# ISL6236A_DEMO.net
KiCad netlist of a schematic drawn in Altium Designer
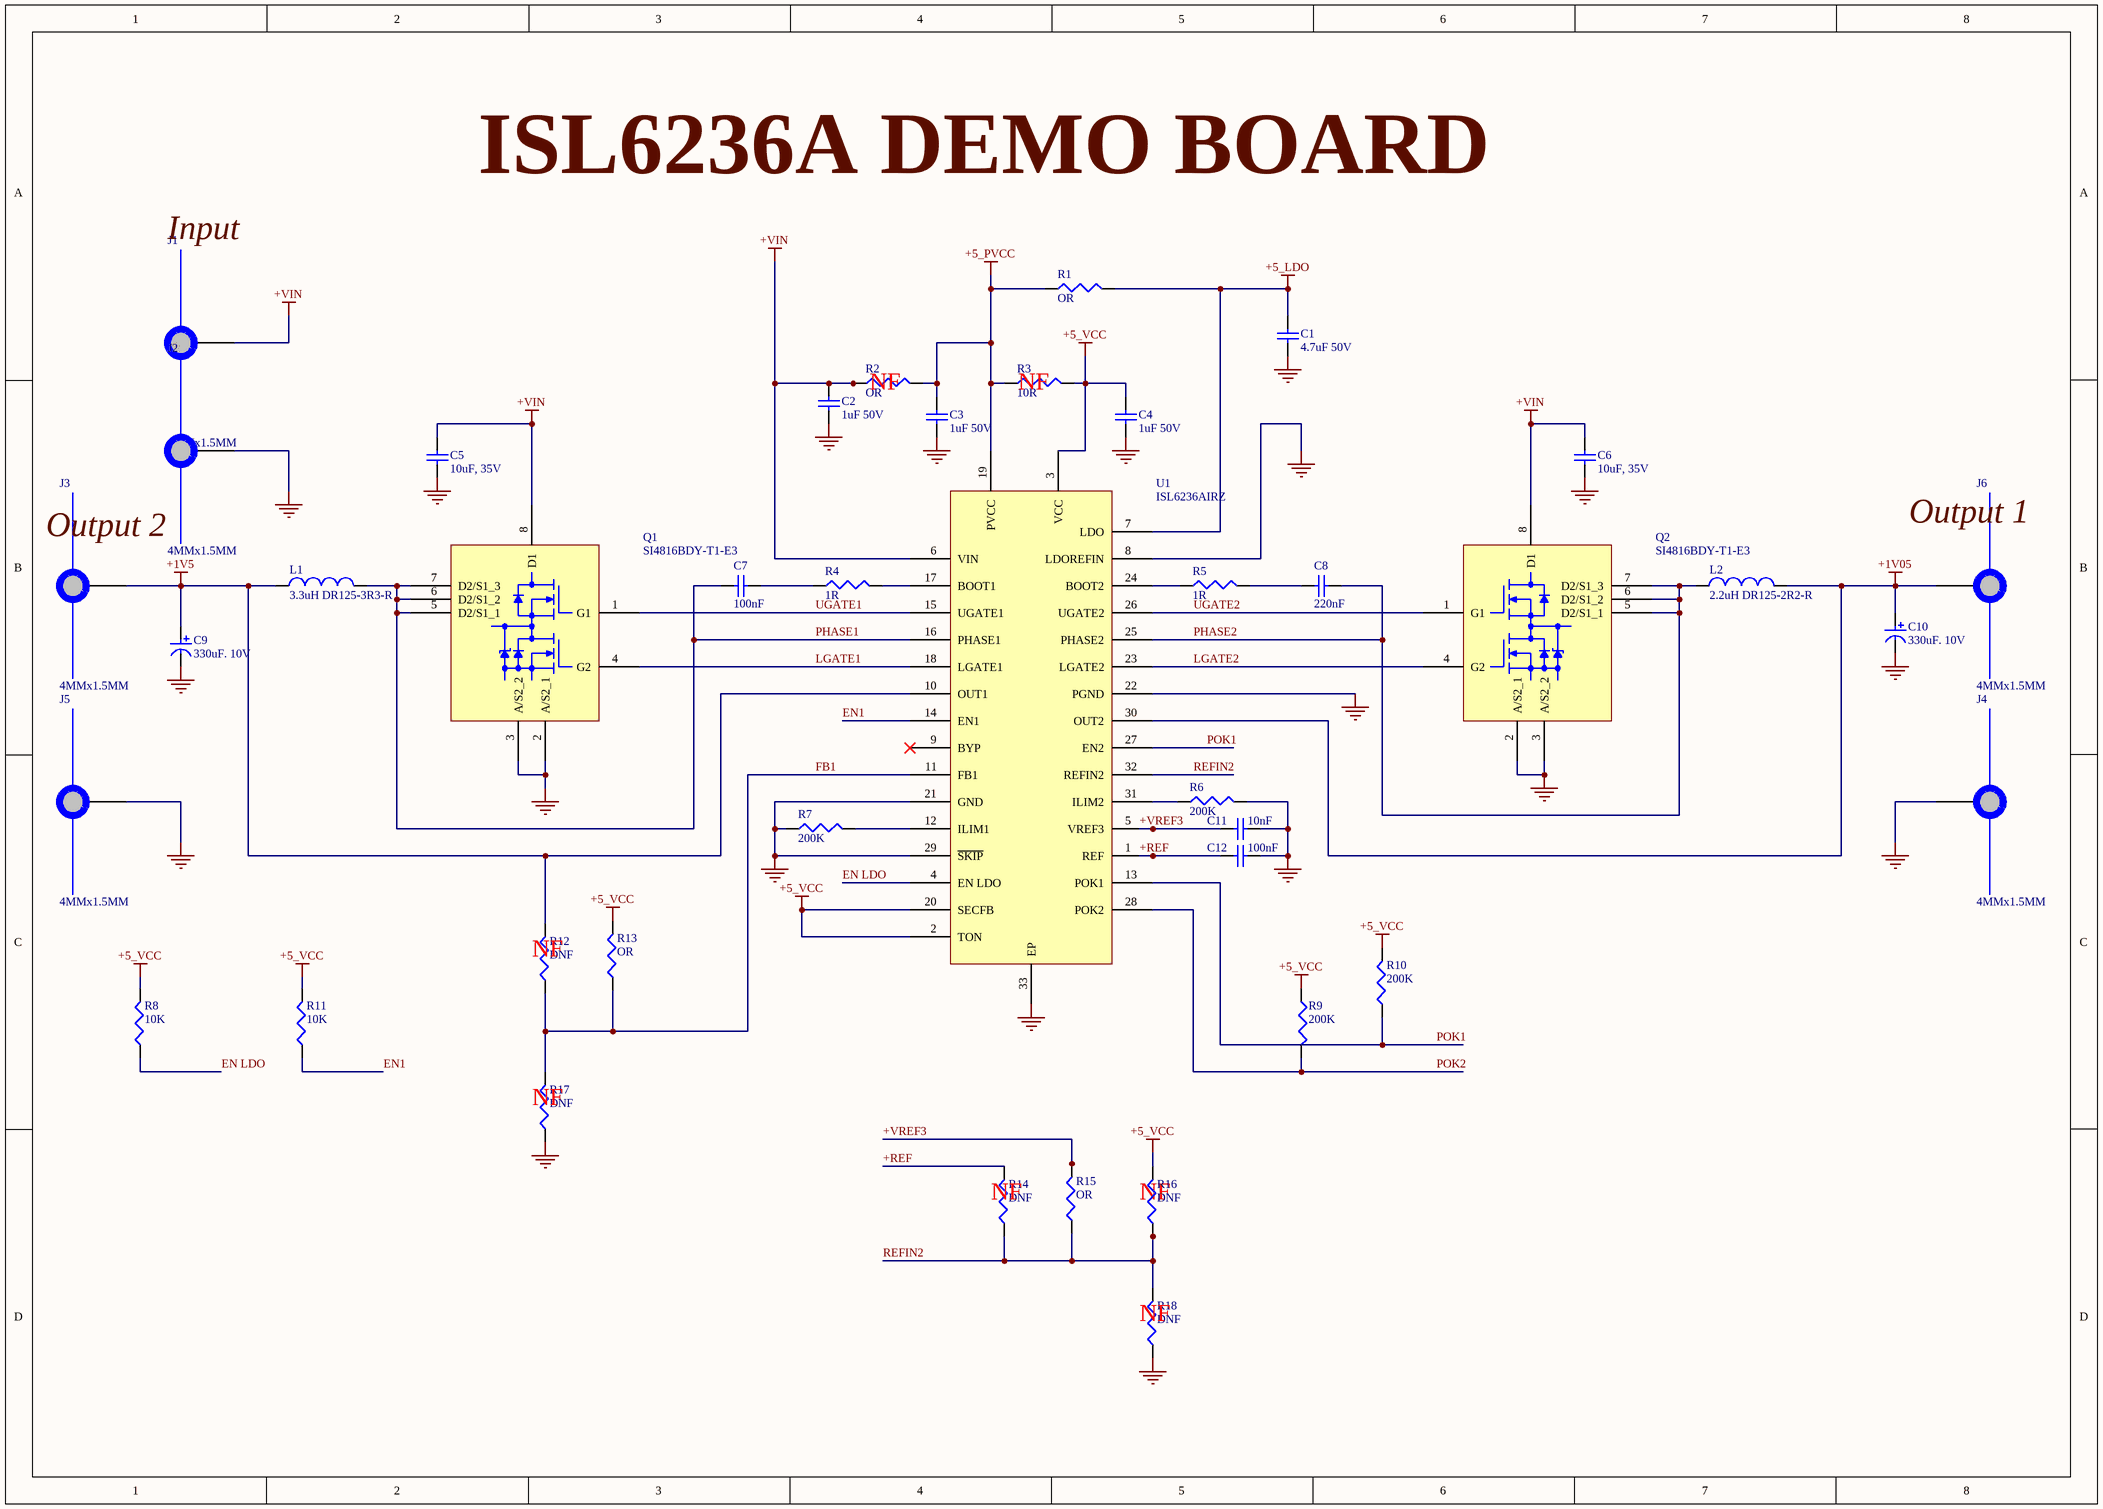
[diagram p0: ISL6236A_DEMO.SchDoc]

(export (version "E")
  (design (tool "Eeschema 10.0.6"))
  (components
    (comp (ref "C1")
      (value "4.7uF 50V")
      (footprint "C1206")
      (description "C Series 1206 4.7 uF 50 V ±10 % Tolerance X5R SMT Multilayer Ceramic Capacitor")
      (fields
        (field (name "MANUFACTURER") "TDK")
        (field (name "MANUFACTURER PART NUMBER") "C3216X5R1H475K160AB")
      )
      (libsource (lib "ISL6236A_DEMO") (part "C3216X5R1H475K160AB"))
    )
    (comp (ref "C2")
      (value "1uF 50V")
      (footprint "C0805")
      (description "Cap Ceramic 1uF 50V X7R 10% SMD 0805 125°C Embossed Plastic T/R")
      (fields
        (field (name "MANUFACTURER") "Samsung")
        (field (name "MANUFACTURER PART NUMBER") "CL21B105KBFNNNG")
      )
      (libsource (lib "ISL6236A_DEMO") (part "CL21B105KBFNNNG"))
    )
    (comp (ref "C3")
      (value "1uF 50V")
      (footprint "C0805")
      (description "Cap Ceramic 1uF 50V X7R 10% SMD 0805 125°C Embossed Plastic T/R")
      (fields
        (field (name "MANUFACTURER") "Samsung")
        (field (name "MANUFACTURER PART NUMBER") "CL21B105KBFNNNG")
      )
      (libsource (lib "ISL6236A_DEMO") (part "CL21B105KBFNNNG"))
    )
    (comp (ref "C4")
      (value "1uF 50V")
      (footprint "C0805")
      (description "Cap Ceramic 1uF 50V X7R 10% SMD 0805 125°C Embossed Plastic T/R")
      (fields
        (field (name "MANUFACTURER") "Samsung")
        (field (name "MANUFACTURER PART NUMBER") "CL21B105KBFNNNG")
      )
      (libsource (lib "ISL6236A_DEMO") (part "CL21B105KBFNNNG"))
    )
    (comp (ref "C5")
      (value "10uF, 35V")
      (footprint "C1210")
      (description "1210 C 10uF Ceramic Multilayer Capacitor; 35 VDC; +85degC; X5R Dielec; +/-10%")
      (fields
        (field (name "MANUFACTURER") "KEMET")
        (field (name "MANUFACTURER PART NUMBER") "C1210C106K6PACTU")
      )
      (libsource (lib "ISL6236A_DEMO") (part "C1210C106K6PACTU"))
    )
    (comp (ref "C6")
      (value "10uF, 35V")
      (footprint "C1210")
      (description "1210 C 10uF Ceramic Multilayer Capacitor; 35 VDC; +85degC; X5R Dielec; +/-10%")
      (fields
        (field (name "MANUFACTURER") "KEMET")
        (field (name "MANUFACTURER PART NUMBER") "C1210C106K6PACTU")
      )
      (libsource (lib "ISL6236A_DEMO") (part "C1210C106K6PACTU"))
    )
    (comp (ref "C7")
      (value "100nF")
      (footprint "C0805")
      (description "Cap Ceramic 0.1uF 50V X7R 10% SMD 2.0 x 1.2 mm 125 C Paper T/R")
      (fields
        (field (name "MANUFACTURER") "KEMET")
        (field (name "MANUFACTURER PART NUMBER") "C0805C104K5RACTU")
      )
      (libsource (lib "ISL6236A_DEMO") (part "C0805C104K5RACTU"))
    )
    (comp (ref "C8")
      (value "220nF")
      (footprint "C0805")
      (description "0805 C 220nF Ceramic Multilayer Capacitor; 50 VDC; +125degC; X7R Dielec; +/-10%")
      (fields
        (field (name "MANUFACTURER") "KEMET")
        (field (name "MANUFACTURER PART NUMBER") "C0805C224K5RACTU")
      )
      (libsource (lib "ISL6236A_DEMO") (part "C0805C224K5RACTU"))
    )
    (comp (ref "C9")
      (value "330uF. 10V")
      (footprint "7343-43")
      (description "Cap Tant Solid 330uF 10V X CASE 20% (7.3 X 4.3 X 4mm) SMD 7343-43 0.004 Ohm 125 C T/R")
      (fields
        (field (name "MANUFACTURER") "KEMET")
        (field (name "MANUFACTURER PART NUMBER") "T530X337M010AHE004")
      )
      (libsource (lib "ISL6236A_DEMO") (part "T530X337M010AHE004"))
    )
    (comp (ref "C10")
      (value "330uF. 10V")
      (footprint "7343-43")
      (description "Cap Tant Solid 330uF 10V X CASE 20% (7.3 X 4.3 X 4mm) SMD 7343-43 0.004 Ohm 125 C T/R")
      (fields
        (field (name "MANUFACTURER") "KEMET")
        (field (name "MANUFACTURER PART NUMBER") "T530X337M010AHE004")
      )
      (libsource (lib "ISL6236A_DEMO") (part "T530X337M010AHE004"))
    )
    (comp (ref "C11")
      (value "10nF")
      (footprint "C0805")
      (description "Cap Ceramic 0.01uF 50V X7R 10% SMD 0805 125C Plastic T/R")
      (fields
        (field (name "MANUFACTURER") "KEMET")
        (field (name "MANUFACTURER PART NUMBER") "C0805C103K5RACTU")
      )
      (libsource (lib "ISL6236A_DEMO") (part "C0805C103K5RACTU"))
    )
    (comp (ref "C12")
      (value "100nF")
      (footprint "C0805")
      (description "Cap Ceramic 0.1uF 50V X7R 10% SMD 2.0 x 1.2 mm 125 C Paper T/R")
      (fields
        (field (name "MANUFACTURER") "KEMET")
        (field (name "MANUFACTURER PART NUMBER") "C0805C104K5RACTU")
      )
      (libsource (lib "ISL6236A_DEMO") (part "C0805C104K5RACTU"))
    )
    (comp (ref "J1")
      (value "4MMx1.5MM")
      (footprint "PAD_WITH_HOLE_4MMx1MM5")
      (description "Pad with a hole 4mmx1.5mm")
      (libsource (lib "ISL6236A_DEMO") (part "PAD_WITH_HOLE_4MMx1MM5"))
    )
    (comp (ref "J2")
      (value "4MMx1.5MM")
      (footprint "PAD_WITH_HOLE_4MMx1MM5")
      (description "Pad with a hole 4mmx1.5mm")
      (libsource (lib "ISL6236A_DEMO") (part "PAD_WITH_HOLE_4MMx1MM5"))
    )
    (comp (ref "J3")
      (value "4MMx1.5MM")
      (footprint "PAD_WITH_HOLE_4MMx1MM5")
      (description "Pad with a hole 4mmx1.5mm")
      (libsource (lib "ISL6236A_DEMO") (part "PAD_WITH_HOLE_4MMx1MM5"))
    )
    (comp (ref "J4")
      (value "4MMx1.5MM")
      (footprint "PAD_WITH_HOLE_4MMx1MM5")
      (description "Pad with a hole 4mmx1.5mm")
      (libsource (lib "ISL6236A_DEMO") (part "PAD_WITH_HOLE_4MMx1MM5"))
    )
    (comp (ref "J5")
      (value "4MMx1.5MM")
      (footprint "PAD_WITH_HOLE_4MMx1MM5")
      (description "Pad with a hole 4mmx1.5mm")
      (libsource (lib "ISL6236A_DEMO") (part "PAD_WITH_HOLE_4MMx1MM5"))
    )
    (comp (ref "J6")
      (value "4MMx1.5MM")
      (footprint "PAD_WITH_HOLE_4MMx1MM5")
      (description "Pad with a hole 4mmx1.5mm")
      (libsource (lib "ISL6236A_DEMO") (part "PAD_WITH_HOLE_4MMx1MM5"))
    )
    (comp (ref "L1")
      (value "3.3uH DR125-3R3-R")
      (footprint "DR125")
      (description "Inductor Power Shielded Drum Core 3.3uH 20% 100KHz Ferrite 9.26A 6.3mOhm DCR T/R")
      (fields
        (field (name "MANUFACTURER") "Eaton Cooper")
        (field (name "MANUFACTURER PART NUMBER") "DR125-3R3-R")
      )
      (libsource (lib "ISL6236A_DEMO") (part "DR125-3R3-R"))
    )
    (comp (ref "L2")
      (value "2.2uH DR125-2R2-R")
      (footprint "DR125")
      (description "FIXED IND 2.2UH 10.9A 4.5 MOHM")
      (fields
        (field (name "MANUFACTURER") "Eaton Cooper")
        (field (name "MANUFACTURER PART NUMBER") "DR125-2R2-R")
      )
      (libsource (lib "ISL6236A_DEMO") (part "DR125-2R2-R"))
    )
    (comp (ref "Q1")
      (value "SI4816BDY-T1-E3")
      (footprint "SO-8")
      (description "Trans Mosfet N-ch 30V 5.8A/8.2A 8-PIN SOIC N T/r")
      (fields (field (name "MANUFACTURER") "Vishay Siliconix"))
      (libsource (lib "ISL6236A_DEMO") (part "SI4816BDY-T1-E3"))
    )
    (comp (ref "Q2")
      (value "SI4816BDY-T1-E3")
      (footprint "SO-8")
      (description "Trans Mosfet N-ch 30V 5.8A/8.2A 8-PIN SOIC N T/r")
      (fields (field (name "MANUFACTURER") "Vishay Siliconix"))
      (libsource (lib "") (part "SI4816BDY-T1-E3_1"))
    )
    (comp (ref "R1")
      (value "OR")
      (footprint "R0805")
      (description "Fixed Resistor, Metal Glaze/thick Film, 0.125W, 0ohm, Surface Mount, 0805")
      (fields
        (field (name "MANUFACTURER") "Yageo")
        (field (name "MANUFACTURER PART NUMBER") "AC0805JR-070RL")
      )
      (libsource (lib "ISL6236A_DEMO") (part "AC0805JR-070RL"))
    )
    (comp (ref "R2")
      (value "OR")
      (footprint "R0805")
      (description "Fixed Resistor, Metal Glaze/thick Film, 0.125W, 0ohm, Surface Mount, 0805")
      (fields
        (field (name "MANUFACTURER") "Yageo")
        (field (name "MANUFACTURER PART NUMBER") "AC0805JR-070RL")
      )
      (libsource (lib "ISL6236A_DEMO") (part "AC0805JR-070RL"))
    )
    (comp (ref "R3")
      (value "10R")
      (footprint "R0805")
      (description "Res Thick Film 0805 10 Ohm 1% 0.125W(1/8W) ±200ppm/C Pad SMD Automotive T/R")
      (fields
        (field (name "MANUFACTURER") "Yageo")
        (field (name "MANUFACTURER PART NUMBER") "AC0805FR-0710RL")
      )
      (libsource (lib "ISL6236A_DEMO") (part "AC0805FR-0710RL"))
    )
    (comp (ref "R4")
      (value "1R")
      (footprint "R0805")
      (description "Res Thick Film 0805 1 Ohm 1% 0.125W(1/8W) ±200ppm/C Pad SMD Automotive T/R")
      (fields
        (field (name "MANUFACTURER") "Yageo")
        (field (name "MANUFACTURER PART NUMBER") "AC0805FR-071RL")
      )
      (libsource (lib "ISL6236A_DEMO") (part "AC0805FR-071RL"))
    )
    (comp (ref "R5")
      (value "1R")
      (footprint "R0805")
      (description "Res Thick Film 0805 1 Ohm 1% 0.125W(1/8W) ±200ppm/C Pad SMD Automotive T/R")
      (fields
        (field (name "MANUFACTURER") "Yageo")
        (field (name "MANUFACTURER PART NUMBER") "AC0805FR-071RL")
      )
      (libsource (lib "ISL6236A_DEMO") (part "AC0805FR-071RL"))
    )
    (comp (ref "R6")
      (value "200K")
      (footprint "R0805")
      (description "Res Thick Film 0805 200K Ohm 1% 0.125W(1/8W) ±100ppm/C Pad SMD Automotive T/R")
      (fields
        (field (name "MANUFACTURER") "Yageo")
        (field (name "MANUFACTURER PART NUMBER") "AC0805FR-07200KL")
      )
      (libsource (lib "ISL6236A_DEMO") (part "AC0805FR-07200KL"))
    )
    (comp (ref "R7")
      (value "200K")
      (footprint "R0805")
      (description "Res Thick Film 0805 200K Ohm 1% 0.125W(1/8W) ±100ppm/C Pad SMD Automotive T/R")
      (fields
        (field (name "MANUFACTURER") "Yageo")
        (field (name "MANUFACTURER PART NUMBER") "AC0805FR-07200KL")
      )
      (libsource (lib "ISL6236A_DEMO") (part "AC0805FR-07200KL"))
    )
    (comp (ref "R8")
      (value "10K")
      (footprint "R0805")
      (description "Res Thick Film 0805 10K Ohm 1% 0.125W(1/8W) ±100ppm/C Pad SMD Automotive T/R")
      (fields
        (field (name "MANUFACTURER") "Yageo")
        (field (name "MANUFACTURER PART NUMBER") "AC0805FR-0710KL")
      )
      (libsource (lib "ISL6236A_DEMO") (part "AC0805FR-0710KL"))
    )
    (comp (ref "R9")
      (value "200K")
      (footprint "R0805")
      (description "Res Thick Film 0805 200K Ohm 1% 0.125W(1/8W) ±100ppm/C Pad SMD Automotive T/R")
      (fields
        (field (name "MANUFACTURER") "Yageo")
        (field (name "MANUFACTURER PART NUMBER") "AC0805FR-07200KL")
      )
      (libsource (lib "ISL6236A_DEMO") (part "AC0805FR-07200KL"))
    )
    (comp (ref "R10")
      (value "200K")
      (footprint "R0805")
      (description "Res Thick Film 0805 200K Ohm 1% 0.125W(1/8W) ±100ppm/C Pad SMD Automotive T/R")
      (fields
        (field (name "MANUFACTURER") "Yageo")
        (field (name "MANUFACTURER PART NUMBER") "AC0805FR-07200KL")
      )
      (libsource (lib "ISL6236A_DEMO") (part "AC0805FR-07200KL"))
    )
    (comp (ref "R11")
      (value "10K")
      (footprint "R0805")
      (description "Res Thick Film 0805 10K Ohm 1% 0.125W(1/8W) ±100ppm/C Pad SMD Automotive T/R")
      (fields
        (field (name "MANUFACTURER") "Yageo")
        (field (name "MANUFACTURER PART NUMBER") "AC0805FR-0710KL")
      )
      (libsource (lib "ISL6236A_DEMO") (part "AC0805FR-0710KL"))
    )
    (comp (ref "R12") (value "DNF") (footprint "R0805") (libsource (lib "ISL6236A_DEMO") (part "RES")))
    (comp (ref "R13")
      (value "OR")
      (footprint "R0805")
      (description "Fixed Resistor, Metal Glaze/thick Film, 0.125W, 0ohm, Surface Mount, 0805")
      (fields
        (field (name "MANUFACTURER") "Yageo")
        (field (name "MANUFACTURER PART NUMBER") "AC0805JR-070RL")
      )
      (libsource (lib "ISL6236A_DEMO") (part "AC0805JR-070RL"))
    )
    (comp (ref "R14") (value "DNF") (footprint "R0805") (libsource (lib "ISL6236A_DEMO") (part "RES")))
    (comp (ref "R15")
      (value "OR")
      (footprint "R0805")
      (description "Fixed Resistor, Metal Glaze/thick Film, 0.125W, 0ohm, Surface Mount, 0805")
      (fields
        (field (name "MANUFACTURER") "Yageo")
        (field (name "MANUFACTURER PART NUMBER") "AC0805JR-070RL")
      )
      (libsource (lib "ISL6236A_DEMO") (part "AC0805JR-070RL"))
    )
    (comp (ref "R16") (value "DNF") (footprint "R0805") (libsource (lib "ISL6236A_DEMO") (part "RES")))
    (comp (ref "R17") (value "DNF") (footprint "R0805") (libsource (lib "ISL6236A_DEMO") (part "RES")))
    (comp (ref "R18") (value "DNF") (footprint "R0805") (libsource (lib "ISL6236A_DEMO") (part "RES")))
    (comp (ref "U1")
      (value "ISL6236AIRZ")
      (footprint "L32.5x5B")
      (description "Soft Sw PWM Cntrlr 2-OUT Power Supply Controller 200KHz/300KHz/400KHz/500KHz 32-Pin QFN EP")
      (fields (field (name "MANUFACTURER") "Renesas"))
      (libsource (lib "ISL6236A_DEMO") (part "ISL6236AIRZ"))
    )
  )
  (nets
    (net (code "1") (name "+1V05") (class "Default")
      (node (ref "C10") (pin "1") (pinfunction "1_1") (pintype "passive"))
      (node (ref "J6") (pin "1") (pinfunction "1_1") (pintype "passive"))
      (node (ref "L2") (pin "2") (pinfunction "2_2") (pintype "passive"))
      (node (ref "U1") (pin "30") (pinfunction "OUT2_30") (pintype "passive"))
    )
    (net (code "2") (name "+1V5") (class "Default")
      (node (ref "C9") (pin "1") (pinfunction "1_1") (pintype "passive"))
      (node (ref "J3") (pin "1") (pinfunction "1_1") (pintype "passive"))
      (node (ref "L1") (pin "1") (pinfunction "1_1") (pintype "passive"))
      (node (ref "R12") (pin "2") (pinfunction "2_2") (pintype "passive"))
      (node (ref "U1") (pin "10") (pinfunction "OUT1_10") (pintype "passive"))
    )
    (net (code "3") (name "+5_LDO") (class "Default")
      (node (ref "C1") (pin "2") (pinfunction "2_2") (pintype "passive"))
      (node (ref "R1") (pin "2") (pinfunction "2_2") (pintype "passive"))
      (node (ref "U1") (pin "7") (pinfunction "LDO_7") (pintype "passive"))
    )
    (net (code "4") (name "+5_PVCC") (class "Default")
      (node (ref "C3") (pin "2") (pinfunction "2_2") (pintype "passive"))
      (node (ref "R1") (pin "1") (pinfunction "1_1") (pintype "passive"))
      (node (ref "R2") (pin "2") (pinfunction "2_2") (pintype "passive"))
      (node (ref "R3") (pin "1") (pinfunction "1_1") (pintype "passive"))
      (node (ref "U1") (pin "19") (pinfunction "PVCC_19") (pintype "passive"))
    )
    (net (code "5") (name "+5_VCC") (class "Default")
      (node (ref "C4") (pin "2") (pinfunction "2_2") (pintype "passive"))
      (node (ref "R10") (pin "2") (pinfunction "2_2") (pintype "passive"))
      (node (ref "R11") (pin "2") (pinfunction "2_2") (pintype "passive"))
      (node (ref "R13") (pin "2") (pinfunction "2_2") (pintype "passive"))
      (node (ref "R16") (pin "2") (pinfunction "2_2") (pintype "passive"))
      (node (ref "R3") (pin "2") (pinfunction "2_2") (pintype "passive"))
      (node (ref "R8") (pin "2") (pinfunction "2_2") (pintype "passive"))
      (node (ref "R9") (pin "1") (pinfunction "1_1") (pintype "passive"))
      (node (ref "U1") (pin "2") (pinfunction "TON_2") (pintype "passive"))
      (node (ref "U1") (pin "20") (pinfunction "SECFB_20") (pintype "passive"))
      (node (ref "U1") (pin "3") (pinfunction "VCC_3") (pintype "passive"))
    )
    (net (code "6") (name "+VIN") (class "Default")
      (node (ref "C2") (pin "2") (pinfunction "2_2") (pintype "passive"))
      (node (ref "C5") (pin "2") (pinfunction "2_2") (pintype "passive"))
      (node (ref "C6") (pin "2") (pinfunction "2_2") (pintype "passive"))
      (node (ref "J1") (pin "1") (pinfunction "1_1") (pintype "passive"))
      (node (ref "Q1") (pin "8") (pinfunction "D1_8") (pintype "passive"))
      (node (ref "Q2") (pin "8") (pinfunction "D1_8") (pintype "passive"))
      (node (ref "R2") (pin "1") (pinfunction "1_1") (pintype "passive"))
      (node (ref "U1") (pin "6") (pinfunction "VIN_6") (pintype "passive"))
    )
    (net (code "7") (name "/+REF") (class "Default")
      (node (ref "C12") (pin "1") (pinfunction "1_1") (pintype "passive"))
      (node (ref "R14") (pin "2") (pinfunction "2_2") (pintype "passive"))
      (node (ref "U1") (pin "1") (pinfunction "REF_1") (pintype "passive"))
    )
    (net (code "8") (name "/+VREF3") (class "Default")
      (node (ref "C11") (pin "1") (pinfunction "1_1") (pintype "passive"))
      (node (ref "R15") (pin "2") (pinfunction "2_2") (pintype "passive"))
      (node (ref "U1") (pin "5") (pinfunction "VREF3_5") (pintype "passive"))
    )
    (net (code "9") (name "/EN LDO") (class "Default")
      (node (ref "R8") (pin "1") (pinfunction "1_1") (pintype "passive"))
      (node (ref "U1") (pin "4") (pinfunction "EN_LDO_4") (pintype "passive"))
    )
    (net (code "10") (name "/EN1") (class "Default")
      (node (ref "R11") (pin "1") (pinfunction "1_1") (pintype "passive"))
      (node (ref "U1") (pin "14") (pinfunction "EN1_14") (pintype "passive"))
    )
    (net (code "11") (name "/FB1") (class "Default")
      (node (ref "R12") (pin "1") (pinfunction "1_1") (pintype "passive"))
      (node (ref "R13") (pin "1") (pinfunction "1_1") (pintype "passive"))
      (node (ref "R17") (pin "2") (pinfunction "2_2") (pintype "passive"))
      (node (ref "U1") (pin "11") (pinfunction "FB1_11") (pintype "passive"))
    )
    (net (code "12") (name "/LGATE1") (class "Default")
      (node (ref "Q1") (pin "4") (pinfunction "G2_4") (pintype "passive"))
      (node (ref "U1") (pin "18") (pinfunction "LGATE1_18") (pintype "passive"))
    )
    (net (code "13") (name "/LGATE2") (class "Default")
      (node (ref "Q2") (pin "4") (pinfunction "G2_4") (pintype "passive"))
      (node (ref "U1") (pin "23") (pinfunction "LGATE2_23") (pintype "passive"))
    )
    (net (code "14") (name "/PHASE1") (class "Default")
      (node (ref "C7") (pin "1") (pinfunction "1_1") (pintype "passive"))
      (node (ref "L1") (pin "2") (pinfunction "2_2") (pintype "passive"))
      (node (ref "Q1") (pin "5") (pinfunction "D2/S1_1_5") (pintype "passive"))
      (node (ref "Q1") (pin "6") (pinfunction "D2/S1_2_6") (pintype "passive"))
      (node (ref "Q1") (pin "7") (pinfunction "D2/S1_3_7") (pintype "passive"))
      (node (ref "U1") (pin "16") (pinfunction "PHASE1_16") (pintype "passive"))
    )
    (net (code "15") (name "/PHASE2") (class "Default")
      (node (ref "C8") (pin "2") (pinfunction "2_2") (pintype "passive"))
      (node (ref "L2") (pin "1") (pinfunction "1_1") (pintype "passive"))
      (node (ref "Q2") (pin "5") (pinfunction "D2/S1_1_5") (pintype "passive"))
      (node (ref "Q2") (pin "6") (pinfunction "D2/S1_2_6") (pintype "passive"))
      (node (ref "Q2") (pin "7") (pinfunction "D2/S1_3_7") (pintype "passive"))
      (node (ref "U1") (pin "25") (pinfunction "PHASE2_25") (pintype "passive"))
    )
    (net (code "16") (name "/POK1") (class "Default")
      (node (ref "R10") (pin "1") (pinfunction "1_1") (pintype "passive"))
      (node (ref "U1") (pin "13") (pinfunction "POK1_13") (pintype "passive"))
      (node (ref "U1") (pin "27") (pinfunction "EN2_27") (pintype "passive"))
    )
    (net (code "17") (name "/POK2") (class "Default")
      (node (ref "R9") (pin "2") (pinfunction "2_2") (pintype "passive"))
      (node (ref "U1") (pin "28") (pinfunction "POK2_28") (pintype "passive"))
    )
    (net (code "18") (name "/REFIN2") (class "Default")
      (node (ref "R14") (pin "1") (pinfunction "1_1") (pintype "passive"))
      (node (ref "R15") (pin "1") (pinfunction "1_1") (pintype "passive"))
      (node (ref "R16") (pin "1") (pinfunction "1_1") (pintype "passive"))
      (node (ref "R18") (pin "2") (pinfunction "2_2") (pintype "passive"))
      (node (ref "U1") (pin "32") (pinfunction "REFIN2_32") (pintype "passive"))
    )
    (net (code "19") (name "/UGATE1") (class "Default")
      (node (ref "Q1") (pin "1") (pinfunction "G1_1") (pintype "passive"))
      (node (ref "U1") (pin "15") (pinfunction "UGATE1_15") (pintype "passive"))
    )
    (net (code "20") (name "/UGATE2") (class "Default")
      (node (ref "Q2") (pin "1") (pinfunction "G1_1") (pintype "passive"))
      (node (ref "U1") (pin "26") (pinfunction "UGATE2_26") (pintype "passive"))
    )
    (net (code "21") (name "GND") (class "Default")
      (node (ref "C1") (pin "1") (pinfunction "1_1") (pintype "passive"))
      (node (ref "C10") (pin "2") (pinfunction "2_2") (pintype "passive"))
      (node (ref "C11") (pin "2") (pinfunction "2_2") (pintype "passive"))
      (node (ref "C12") (pin "2") (pinfunction "2_2") (pintype "passive"))
      (node (ref "C2") (pin "1") (pinfunction "1_1") (pintype "passive"))
      (node (ref "C3") (pin "1") (pinfunction "1_1") (pintype "passive"))
      (node (ref "C4") (pin "1") (pinfunction "1_1") (pintype "passive"))
      (node (ref "C5") (pin "1") (pinfunction "1_1") (pintype "passive"))
      (node (ref "C6") (pin "1") (pinfunction "1_1") (pintype "passive"))
      (node (ref "C9") (pin "2") (pinfunction "2_2") (pintype "passive"))
      (node (ref "J2") (pin "1") (pinfunction "1_1") (pintype "passive"))
      (node (ref "J4") (pin "1") (pinfunction "1_1") (pintype "passive"))
      (node (ref "J5") (pin "1") (pinfunction "1_1") (pintype "passive"))
      (node (ref "Q1") (pin "2") (pinfunction "A/S2_1_2") (pintype "passive"))
      (node (ref "Q1") (pin "3") (pinfunction "A/S2_2_3") (pintype "passive"))
      (node (ref "Q2") (pin "2") (pinfunction "A/S2_1_2") (pintype "passive"))
      (node (ref "Q2") (pin "3") (pinfunction "A/S2_2_3") (pintype "passive"))
      (node (ref "R17") (pin "1") (pinfunction "1_1") (pintype "passive"))
      (node (ref "R18") (pin "1") (pinfunction "1_1") (pintype "passive"))
      (node (ref "R6") (pin "2") (pinfunction "2_2") (pintype "passive"))
      (node (ref "R7") (pin "1") (pinfunction "1_1") (pintype "passive"))
      (node (ref "U1") (pin "21") (pinfunction "GND_21") (pintype "passive"))
      (node (ref "U1") (pin "22") (pinfunction "PGND_22") (pintype "passive"))
      (node (ref "U1") (pin "29") (pinfunction "~{SKIP}_29") (pintype "passive"))
      (node (ref "U1") (pin "33") (pinfunction "EP_33") (pintype "passive"))
      (node (ref "U1") (pin "8") (pinfunction "LDOREFIN_8") (pintype "passive"))
    )
    (net (code "22") (name "Net-(C7-Pad2)") (class "Default")
      (node (ref "C7") (pin "2") (pinfunction "2_2") (pintype "passive"))
      (node (ref "R4") (pin "1") (pinfunction "1_1") (pintype "passive"))
    )
    (net (code "23") (name "Net-(C8-Pad1)") (class "Default")
      (node (ref "C8") (pin "1") (pinfunction "1_1") (pintype "passive"))
      (node (ref "R5") (pin "2") (pinfunction "2_2") (pintype "passive"))
    )
    (net (code "24") (name "Net-(U1-BOOT1)") (class "Default")
      (node (ref "R4") (pin "2") (pinfunction "2_2") (pintype "passive"))
      (node (ref "U1") (pin "17") (pinfunction "BOOT1_17") (pintype "passive"))
    )
    (net (code "25") (name "Net-(U1-BOOT2)") (class "Default")
      (node (ref "R5") (pin "1") (pinfunction "1_1") (pintype "passive"))
      (node (ref "U1") (pin "24") (pinfunction "BOOT2_24") (pintype "passive"))
    )
    (net (code "26") (name "Net-(U1-ILIM1)") (class "Default")
      (node (ref "R7") (pin "2") (pinfunction "2_2") (pintype "passive"))
      (node (ref "U1") (pin "12") (pinfunction "ILIM1_12") (pintype "passive"))
    )
    (net (code "27") (name "Net-(U1-ILIM2)") (class "Default")
      (node (ref "R6") (pin "1") (pinfunction "1_1") (pintype "passive"))
      (node (ref "U1") (pin "31") (pinfunction "ILIM2_31") (pintype "passive"))
    )
    (net (code "28") (name "unconnected-(U1-BYP-Pad9)") (class "Default")
      (node (ref "U1") (pin "9") (pinfunction "BYP_9") (pintype "passive+no_connect"))
    )
  )
)
